# ble112_breakout_board_v10.net
KiCad netlist of a schematic drawn in EAGLE
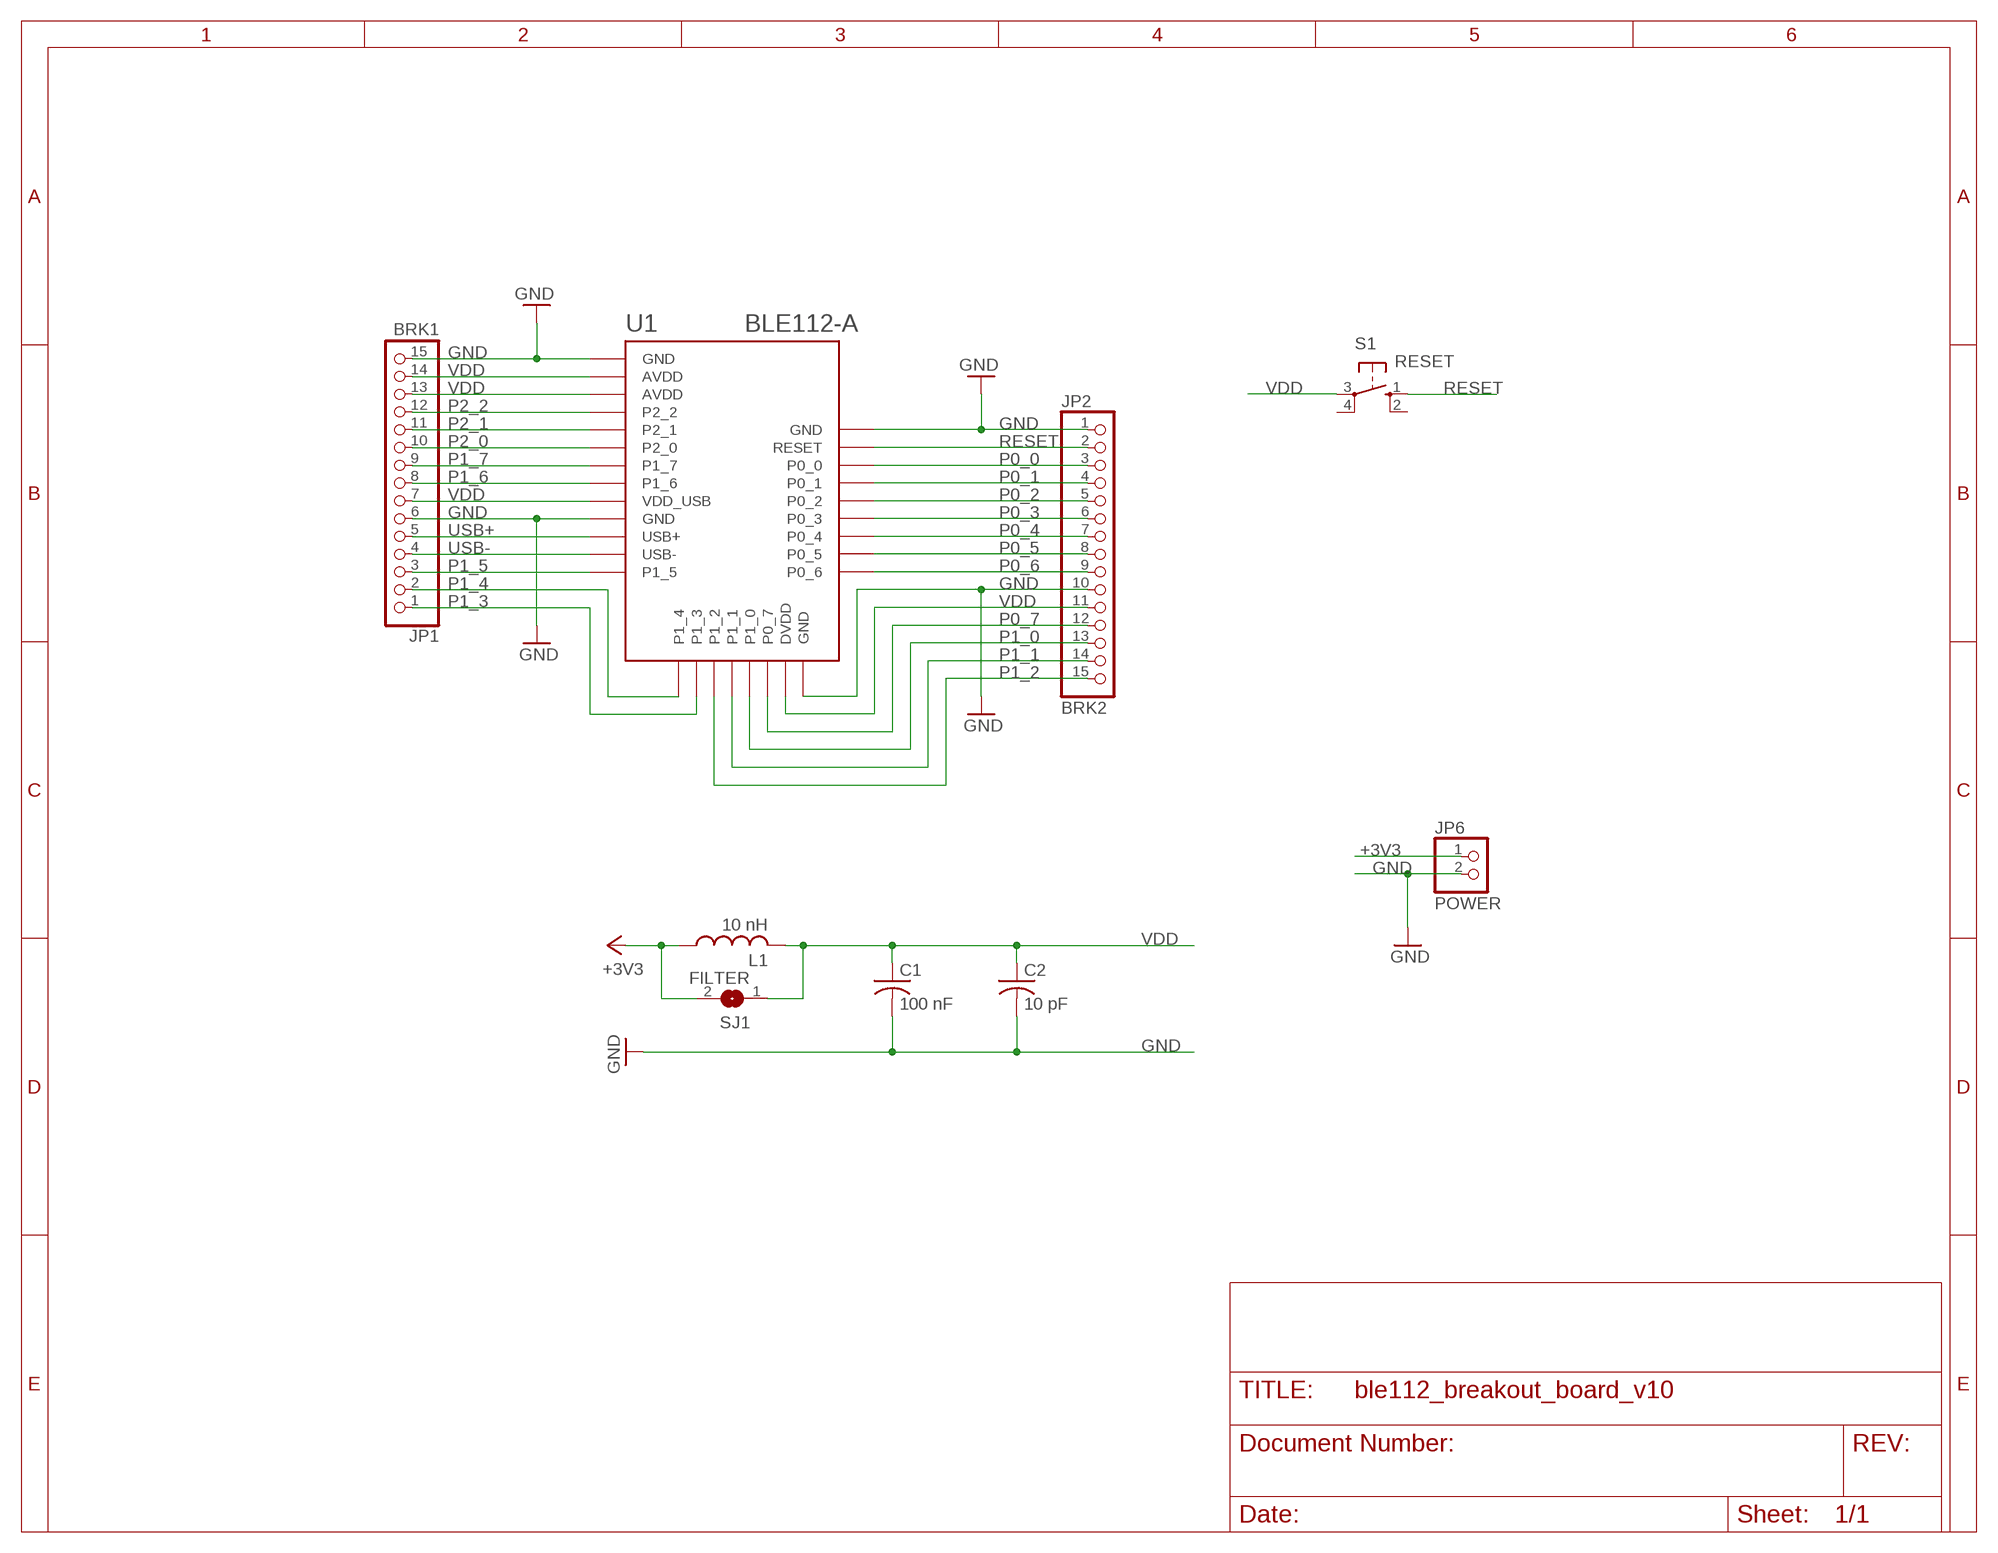
[diagram p0: schematic, sheet 1]

(export (version "E")
  (design (tool "Eeschema 10.0.6"))
  (components
    (comp (ref "C1")
      (value "100 nF")
      (footprint "eagle-import:C025-025X050")
      (libsource (lib "eagle-import") (part "C-US025-025X050"))
    )
    (comp (ref "C2")
      (value "10 pF")
      (footprint "eagle-import:C025-025X050")
      (libsource (lib "eagle-import") (part "C-US025-025X050"))
    )
    (comp (ref "JP1")
      (value "BRK1")
      (footprint "eagle-import:1X15")
      (libsource (lib "eagle-import") (part "PINHD-1X15"))
    )
    (comp (ref "JP2")
      (value "BRK2")
      (footprint "eagle-import:1X15")
      (libsource (lib "eagle-import") (part "PINHD-1X15"))
    )
    (comp (ref "JP6")
      (value "POWER")
      (footprint "eagle-import:1X02")
      (libsource (lib "eagle-import") (part "PINHD-1X2"))
    )
    (comp (ref "L1")
      (value "10 nH")
      (footprint "eagle-import:0204_7")
      (libsource (lib "eagle-import") (part "L-US0204/7"))
    )
    (comp (ref "S1")
      (value "RESET")
      (footprint "eagle-import:B3F-10XX")
      (fields (field (name "MPN") "B3F-1000"))
      (libsource (lib "eagle-import") (part "10-XX"))
    )
    (comp (ref "SJ1")
      (value "FILTER")
      (footprint "eagle-import:SJ")
      (libsource (lib "eagle-import") (part "SJ"))
    )
    (comp (ref "U1")
      (value "BLE112-A")
      (footprint "eagle-import:BLE112-A")
      (libsource (lib "eagle-import") (part "BLE112-A-VISUAL"))
    )
  )
  (nets
    (net (code "1") (name "+3V3") (class "Default")
      (node (ref "JP6") (pin "1") (pinfunction "1_1") (pintype "passive"))
      (node (ref "L1") (pin "1") (pinfunction "1_1") (pintype "passive"))
      (node (ref "SJ1") (pin "2") (pinfunction "2_2") (pintype "passive"))
    )
    (net (code "2") (name "/P0_0") (class "Default")
      (node (ref "JP2") (pin "3") (pinfunction "3_3") (pintype "passive"))
      (node (ref "U1") (pin "P0_0") (pinfunction "P0_0_P0_0") (pintype "bidirectional"))
    )
    (net (code "3") (name "/P0_1") (class "Default")
      (node (ref "JP2") (pin "4") (pinfunction "4_4") (pintype "passive"))
      (node (ref "U1") (pin "P0_1") (pinfunction "P0_1_P0_1") (pintype "bidirectional"))
    )
    (net (code "4") (name "/P0_2") (class "Default")
      (node (ref "JP2") (pin "5") (pinfunction "5_5") (pintype "passive"))
      (node (ref "U1") (pin "P0_2") (pinfunction "P0_2_P0_2") (pintype "bidirectional"))
    )
    (net (code "5") (name "/P0_3") (class "Default")
      (node (ref "JP2") (pin "6") (pinfunction "6_6") (pintype "passive"))
      (node (ref "U1") (pin "P0_3") (pinfunction "P0_3_P0_3") (pintype "bidirectional"))
    )
    (net (code "6") (name "/P0_4") (class "Default")
      (node (ref "JP2") (pin "7") (pinfunction "7_7") (pintype "passive"))
      (node (ref "U1") (pin "P0_4") (pinfunction "P0_4_P0_4") (pintype "bidirectional"))
    )
    (net (code "7") (name "/P0_5") (class "Default")
      (node (ref "JP2") (pin "8") (pinfunction "8_8") (pintype "passive"))
      (node (ref "U1") (pin "P0_5") (pinfunction "P0_5_P0_5") (pintype "bidirectional"))
    )
    (net (code "8") (name "/P0_6") (class "Default")
      (node (ref "JP2") (pin "9") (pinfunction "9_9") (pintype "passive"))
      (node (ref "U1") (pin "P0_6") (pinfunction "P0_6_P0_6") (pintype "bidirectional"))
    )
    (net (code "9") (name "/P0_7") (class "Default")
      (node (ref "JP2") (pin "12") (pinfunction "12_12") (pintype "passive"))
      (node (ref "U1") (pin "P0_7") (pinfunction "P0_7_P0_7") (pintype "bidirectional"))
    )
    (net (code "10") (name "/P1_0") (class "Default")
      (node (ref "JP2") (pin "13") (pinfunction "13_13") (pintype "passive"))
      (node (ref "U1") (pin "P1_0") (pinfunction "P1_0_P1_0") (pintype "bidirectional"))
    )
    (net (code "11") (name "/P1_1") (class "Default")
      (node (ref "JP2") (pin "14") (pinfunction "14_14") (pintype "passive"))
      (node (ref "U1") (pin "P1_1") (pinfunction "P1_1_P1_1") (pintype "bidirectional"))
    )
    (net (code "12") (name "/P1_2") (class "Default")
      (node (ref "JP2") (pin "15") (pinfunction "15_15") (pintype "passive"))
      (node (ref "U1") (pin "P1_2") (pinfunction "P1_2_P1_2") (pintype "bidirectional"))
    )
    (net (code "13") (name "/P1_3") (class "Default")
      (node (ref "JP1") (pin "1") (pinfunction "1_1") (pintype "passive"))
      (node (ref "U1") (pin "P1_3") (pinfunction "P1_3_P1_3") (pintype "bidirectional"))
    )
    (net (code "14") (name "/P1_4") (class "Default")
      (node (ref "JP1") (pin "2") (pinfunction "2_2") (pintype "passive"))
      (node (ref "U1") (pin "P1_4") (pinfunction "P1_4_P1_4") (pintype "bidirectional"))
    )
    (net (code "15") (name "/P1_5") (class "Default")
      (node (ref "JP1") (pin "3") (pinfunction "3_3") (pintype "passive"))
      (node (ref "U1") (pin "P1_5") (pinfunction "P1_5_P1_5") (pintype "bidirectional"))
    )
    (net (code "16") (name "/P1_6") (class "Default")
      (node (ref "JP1") (pin "8") (pinfunction "8_8") (pintype "passive"))
      (node (ref "U1") (pin "P1_6") (pinfunction "P1_6_P1_6") (pintype "bidirectional"))
    )
    (net (code "17") (name "/P1_7") (class "Default")
      (node (ref "JP1") (pin "9") (pinfunction "9_9") (pintype "passive"))
      (node (ref "U1") (pin "P1_7") (pinfunction "P1_7_P1_7") (pintype "bidirectional"))
    )
    (net (code "18") (name "/P2_0") (class "Default")
      (node (ref "JP1") (pin "10") (pinfunction "10_10") (pintype "passive"))
      (node (ref "U1") (pin "P2_0") (pinfunction "P2_0_P2_0") (pintype "bidirectional"))
    )
    (net (code "19") (name "/P2_1") (class "Default")
      (node (ref "JP1") (pin "11") (pinfunction "11_11") (pintype "passive"))
      (node (ref "U1") (pin "P2_1") (pinfunction "P2_1_P2_1") (pintype "bidirectional"))
    )
    (net (code "20") (name "/P2_2") (class "Default")
      (node (ref "JP1") (pin "12") (pinfunction "12_12") (pintype "passive"))
      (node (ref "U1") (pin "P2_2") (pinfunction "P2_2_P2_2") (pintype "bidirectional"))
    )
    (net (code "21") (name "/RESET") (class "Default")
      (node (ref "JP2") (pin "2") (pinfunction "2_2") (pintype "passive"))
      (node (ref "S1") (pin "1") (pinfunction "S_1") (pintype "passive"))
      (node (ref "U1") (pin "RESET") (pinfunction "RESET_RESET") (pintype "input"))
    )
    (net (code "22") (name "/USB+") (class "Default")
      (node (ref "JP1") (pin "5") (pinfunction "5_5") (pintype "passive"))
      (node (ref "U1") (pin "USB+") (pinfunction "USB+_USB+") (pintype "bidirectional"))
    )
    (net (code "23") (name "/USB-") (class "Default")
      (node (ref "JP1") (pin "4") (pinfunction "4_4") (pintype "passive"))
      (node (ref "U1") (pin "USB-") (pinfunction "USB-_USB-") (pintype "bidirectional"))
    )
    (net (code "24") (name "/VDD") (class "Default")
      (node (ref "C1") (pin "1") (pinfunction "1_1") (pintype "passive"))
      (node (ref "C2") (pin "1") (pinfunction "1_1") (pintype "passive"))
      (node (ref "JP1") (pin "13") (pinfunction "13_13") (pintype "passive"))
      (node (ref "JP1") (pin "14") (pinfunction "14_14") (pintype "passive"))
      (node (ref "JP1") (pin "7") (pinfunction "7_7") (pintype "passive"))
      (node (ref "JP2") (pin "11") (pinfunction "11_11") (pintype "passive"))
      (node (ref "L1") (pin "2") (pinfunction "2_2") (pintype "passive"))
      (node (ref "S1") (pin "3") (pinfunction "P_3") (pintype "passive"))
      (node (ref "SJ1") (pin "1") (pinfunction "1_1") (pintype "passive"))
      (node (ref "U1") (pin "AVDD1") (pinfunction "AVDD_AVDD1") (pintype "power_in"))
      (node (ref "U1") (pin "AVDD2") (pinfunction "AVDD_AVDD2") (pintype "power_in"))
      (node (ref "U1") (pin "DVDD") (pinfunction "DVDD_DVDD") (pintype "power_in"))
      (node (ref "U1") (pin "VDD_USB") (pinfunction "VDD_USB_VDD_USB") (pintype "power_in"))
    )
    (net (code "25") (name "GND") (class "Default")
      (node (ref "C1") (pin "2") (pinfunction "2_2") (pintype "passive"))
      (node (ref "C2") (pin "2") (pinfunction "2_2") (pintype "passive"))
      (node (ref "JP1") (pin "15") (pinfunction "15_15") (pintype "passive"))
      (node (ref "JP1") (pin "6") (pinfunction "6_6") (pintype "passive"))
      (node (ref "JP2") (pin "1") (pinfunction "1_1") (pintype "passive"))
      (node (ref "JP2") (pin "10") (pinfunction "10_10") (pintype "passive"))
      (node (ref "JP6") (pin "2") (pinfunction "2_2") (pintype "passive"))
      (node (ref "U1") (pin "GND1") (pinfunction "GND_GND1") (pintype "power_in"))
      (node (ref "U1") (pin "GND2") (pinfunction "GND_GND2") (pintype "power_in"))
      (node (ref "U1") (pin "GND3") (pinfunction "GND_GND3") (pintype "power_in"))
      (node (ref "U1") (pin "GND4") (pinfunction "GND_GND4") (pintype "power_in"))
    )
    (net (code "26") (name "unconnected-(S1-P1-Pad4)") (class "Default")
      (node (ref "S1") (pin "4") (pinfunction "P1_4") (pintype "passive"))
    )
    (net (code "27") (name "unconnected-(S1-S1-Pad2)") (class "Default")
      (node (ref "S1") (pin "2") (pinfunction "S1_2") (pintype "passive"))
    )
  )
)
